# accelerometer.net
KiCad netlist of a schematic drawn in Altium Designer
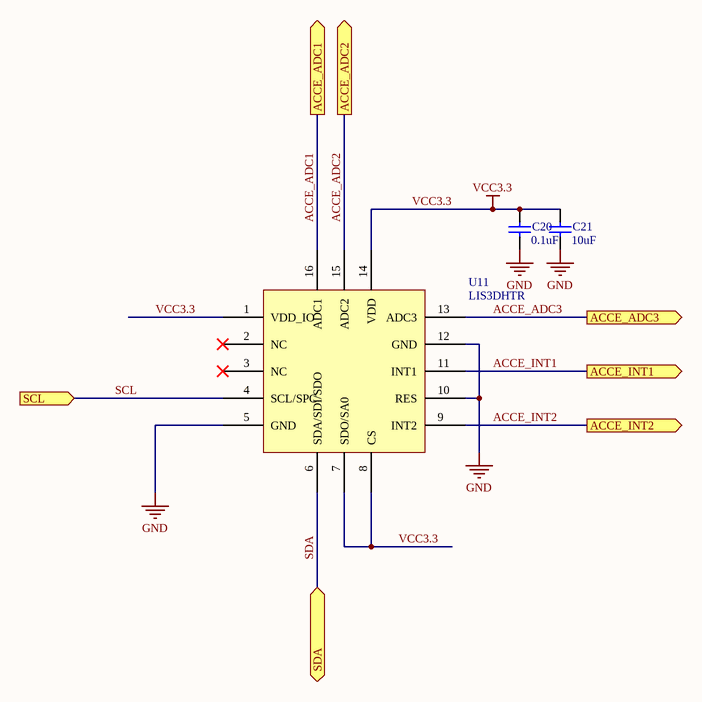
[diagram p0: accelerometer.SchDoc]

(export (version "E")
  (design (tool "Eeschema 10.0.6"))
  (components
    (comp (ref "C20")
      (value "0.1uF")
      (footprint "1608[0603]")
      (description "Capacitor (Semiconductor SIM Model)")
      (fields (field (name "Comment") "Cap Semi") (field (name "PUBLISHER") "Altium Limited"))
      (libsource (lib "Miscellaneous Devices") (part "Cap Semi"))
    )
    (comp (ref "C21")
      (value "10uF")
      (footprint "1608[0603]")
      (description "Capacitor (Semiconductor SIM Model)")
      (fields (field (name "Comment") "Cap Semi") (field (name "PUBLISHER") "Altium Limited"))
      (libsource (lib "Miscellaneous Devices") (part "Cap Semi"))
    )
    (comp (ref "U11")
      (value "LIS3DHTR")
      (footprint "LGA-16")
      (description "MEMS digital output motion sensor")
      (libsource (lib "ultrasounic") (part "LIS3DHTR"))
    )
  )
  (nets
    (net (code "1") (name "/ACCE_ADC1") (class "Default")
      (node (ref "U11") (pin "16") (pinfunction "ADC1_16") (pintype "passive"))
    )
    (net (code "2") (name "/ACCE_ADC2") (class "Default")
      (node (ref "U11") (pin "15") (pinfunction "ADC2_15") (pintype "passive"))
    )
    (net (code "3") (name "/ACCE_ADC3") (class "Default")
      (node (ref "U11") (pin "13") (pinfunction "ADC3_13") (pintype "passive"))
    )
    (net (code "4") (name "/ACCE_INT1") (class "Default")
      (node (ref "U11") (pin "11") (pinfunction "INT1_11") (pintype "passive"))
    )
    (net (code "5") (name "/ACCE_INT2") (class "Default")
      (node (ref "U11") (pin "9") (pinfunction "INT2_9") (pintype "passive"))
    )
    (net (code "6") (name "/SCL") (class "Default")
      (node (ref "U11") (pin "4") (pinfunction "SCL/SPC_4") (pintype "passive"))
    )
    (net (code "7") (name "/SDA") (class "Default")
      (node (ref "U11") (pin "6") (pinfunction "SDA/SDI/SDO_6") (pintype "passive"))
    )
    (net (code "8") (name "GND") (class "Default")
      (node (ref "C20") (pin "1") (pinfunction "1_1") (pintype "passive"))
      (node (ref "C21") (pin "1") (pinfunction "1_1") (pintype "passive"))
      (node (ref "U11") (pin "10") (pinfunction "RES_10") (pintype "passive"))
      (node (ref "U11") (pin "12") (pinfunction "GND_12") (pintype "passive"))
      (node (ref "U11") (pin "5") (pinfunction "GND_5") (pintype "passive"))
    )
    (net (code "9") (name "VCC3.3") (class "Default")
      (node (ref "C20") (pin "2") (pinfunction "2_2") (pintype "passive"))
      (node (ref "C21") (pin "2") (pinfunction "2_2") (pintype "passive"))
      (node (ref "U11") (pin "1") (pinfunction "VDD_IO_1") (pintype "passive"))
      (node (ref "U11") (pin "14") (pinfunction "VDD_14") (pintype "passive"))
      (node (ref "U11") (pin "7") (pinfunction "SDO/SA0_7") (pintype "passive"))
      (node (ref "U11") (pin "8") (pinfunction "CS_8") (pintype "passive"))
    )
    (net (code "10") (name "unconnected-(U11-NC-Pad2)") (class "Default")
      (node (ref "U11") (pin "2") (pinfunction "NC_2") (pintype "passive+no_connect"))
    )
    (net (code "11") (name "unconnected-(U11-NC-Pad3)") (class "Default")
      (node (ref "U11") (pin "3") (pinfunction "NC_3") (pintype "passive+no_connect"))
    )
  )
)
